# PCBv4.net
KiCad netlist of a schematic drawn in Altium Designer
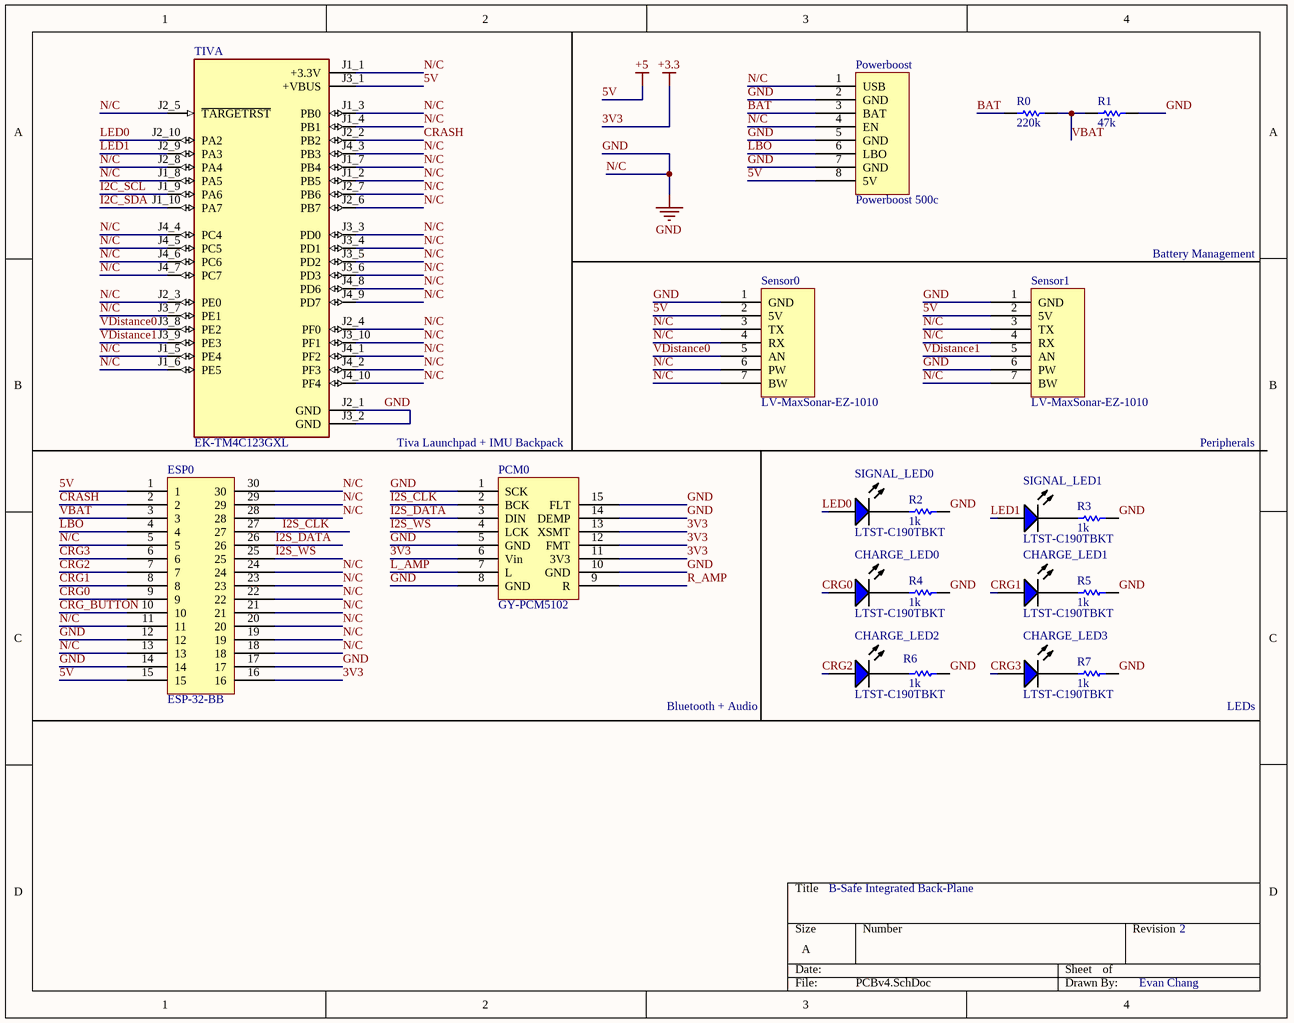
[diagram p0: PCBv4.SchDoc]

(export (version "E")
  (design (tool "Eeschema 10.0.6"))
  (components
    (comp (ref "CHARGE_LED0")
      (value "LTST-C190TBKT")
      (footprint "LTST-C190TBKT-2_V")
      (description "LED Uni-Color Blue, 76 mW, 20 mA, -20 to 80 degC, 2-Pin SMD, RoHS, Tape and Reel")
      (fields (field (name "MANUFACTURER") "Lite-On"))
      (libsource (lib "Evan Chang work on PCB") (part "LED-BLUE-AK-2"))
    )
    (comp (ref "CHARGE_LED1")
      (value "LTST-C190TBKT")
      (footprint "LTST-C190TBKT-2_V")
      (description "LED Uni-Color Blue, 76 mW, 20 mA, -20 to 80 degC, 2-Pin SMD, RoHS, Tape and Reel")
      (fields (field (name "MANUFACTURER") "Lite-On"))
      (libsource (lib "Evan Chang work on PCB") (part "LED-BLUE-AK-2"))
    )
    (comp (ref "CHARGE_LED2")
      (value "LTST-C190TBKT")
      (footprint "LTST-C190TBKT-2_V")
      (description "LED Uni-Color Blue, 76 mW, 20 mA, -20 to 80 degC, 2-Pin SMD, RoHS, Tape and Reel")
      (fields (field (name "MANUFACTURER") "Lite-On"))
      (libsource (lib "Evan Chang work on PCB") (part "LED-BLUE-AK-2"))
    )
    (comp (ref "CHARGE_LED3")
      (value "LTST-C190TBKT")
      (footprint "LTST-C190TBKT-2_V")
      (description "LED Uni-Color Blue, 76 mW, 20 mA, -20 to 80 degC, 2-Pin SMD, RoHS, Tape and Reel")
      (fields (field (name "MANUFACTURER") "Lite-On"))
      (libsource (lib "Evan Chang work on PCB") (part "LED-BLUE-AK-2"))
    )
    (comp (ref "ESP0")
      (value "ESP-32-BB")
      (footprint "ESP-32-BB-Footprint-1")
      (description "Breakoutboard for ESP-32-BB")
      (libsource (lib "Evan Chang work on PCB") (part "ESP-32-BB-Symbol-1"))
    )
    (comp (ref "PCM0")
      (value "GY-PCM5102")
      (footprint "GY-PCM5102-Footprint-1")
      (description "breakout board for pcm")
      (libsource (lib "Evan Chang work on PCB") (part "GY-PCM5102-Symbol-1"))
    )
    (comp (ref "Powerboost")
      (value "Powerboost 500c")
      (footprint "Powerboost 500c-Footprint-1")
      (description "Breakout board component for Adafruit Powerboost 500c")
      (libsource (lib "Evan Chang work on PCB") (part "Powerboost 500c-Symbol-1"))
    )
    (comp (ref "R0")
      (value "220k")
      (footprint "RESC1005X40X25ML05T10")
      (description "Chip Resistor, 51 KOhm, +/- 5%, 0.063 W, -55 to 155 degC, 0402 (1005 Metric)")
      (fields (field (name "POWER") "63mW") (field (name "TOLERANCE") "5%"))
      (libsource (lib "Evan Chang work on PCB") (part "RES-2"))
    )
    (comp (ref "R1")
      (value "47k")
      (footprint "RESC1005X40X25ML05T10")
      (description "Chip Resistor, 51 KOhm, +/- 5%, 0.063 W, -55 to 155 degC, 0402 (1005 Metric)")
      (fields (field (name "POWER") "63mW") (field (name "TOLERANCE") "5%"))
      (libsource (lib "Evan Chang work on PCB") (part "RES-2"))
    )
    (comp (ref "R2")
      (value "1k")
      (footprint "RESC3116X70X50ML13T20")
      (description "Chip Resistor, 1 KOhm, +/- 1%, 0.25 W, -55 to 155 degC, 1206 (3216 Metric)")
      (fields (field (name "TOLERANCE") "1%") (field (name "POWER") "250mW"))
      (libsource (lib "Evan Chang work on PCB") (part "RES-2"))
    )
    (comp (ref "R3")
      (value "1k")
      (footprint "RESC3116X70X50ML13T20")
      (description "Chip Resistor, 1 KOhm, +/- 1%, 0.25 W, -55 to 155 degC, 1206 (3216 Metric)")
      (fields (field (name "TOLERANCE") "1%") (field (name "POWER") "250mW"))
      (libsource (lib "Evan Chang work on PCB") (part "RES-2"))
    )
    (comp (ref "R4")
      (value "1k")
      (footprint "RESC3116X70X50ML13T20")
      (description "Chip Resistor, 1 KOhm, +/- 1%, 0.25 W, -55 to 155 degC, 1206 (3216 Metric)")
      (fields (field (name "TOLERANCE") "1%") (field (name "POWER") "250mW"))
      (libsource (lib "Evan Chang work on PCB") (part "RES-2"))
    )
    (comp (ref "R5")
      (value "1k")
      (footprint "RESC3116X70X50ML13T20")
      (description "Chip Resistor, 1 KOhm, +/- 1%, 0.25 W, -55 to 155 degC, 1206 (3216 Metric)")
      (fields (field (name "TOLERANCE") "1%") (field (name "POWER") "250mW"))
      (libsource (lib "Evan Chang work on PCB") (part "RES-2"))
    )
    (comp (ref "R6")
      (value "1k")
      (footprint "RESC3116X70X50ML13T20")
      (description "Chip Resistor, 1 KOhm, +/- 1%, 0.25 W, -55 to 155 degC, 1206 (3216 Metric)")
      (fields (field (name "TOLERANCE") "1%") (field (name "POWER") "250mW"))
      (libsource (lib "Evan Chang work on PCB") (part "RES-2"))
    )
    (comp (ref "R7")
      (value "1k")
      (footprint "RESC3116X70X50ML13T20")
      (description "Chip Resistor, 1 KOhm, +/- 1%, 0.25 W, -55 to 155 degC, 1206 (3216 Metric)")
      (fields (field (name "TOLERANCE") "1%") (field (name "POWER") "250mW"))
      (libsource (lib "Evan Chang work on PCB") (part "RES-2"))
    )
    (comp (ref "Sensor0")
      (value "LV-MaxSonar-EZ-1010")
      (footprint "LV-MaxSonar-EZ-1010-Footprint-1")
      (description "Ultrasonic sensor")
      (libsource (lib "Evan Chang work on PCB") (part "LV-Ma-Symbol-1"))
    )
    (comp (ref "Sensor1")
      (value "LV-MaxSonar-EZ-1010")
      (footprint "LV-MaxSonar-EZ-1010-Footprint-1")
      (description "Ultrasonic sensor")
      (libsource (lib "Evan Chang work on PCB") (part "LV-Ma-Symbol-1"))
    )
    (comp (ref "SIGNAL_LED0")
      (value "LTST-C190TBKT")
      (footprint "LTST-C190TBKT-2_V")
      (description "LED Uni-Color Blue, 76 mW, 20 mA, -20 to 80 degC, 2-Pin SMD, RoHS, Tape and Reel")
      (fields (field (name "MANUFACTURER") "Lite-On"))
      (libsource (lib "Evan Chang work on PCB") (part "LED-BLUE-AK-2"))
    )
    (comp (ref "SIGNAL_LED1")
      (value "LTST-C190TBKT")
      (footprint "LTST-C190TBKT-2_V")
      (description "LED Uni-Color Blue, 76 mW, 20 mA, -20 to 80 degC, 2-Pin SMD, RoHS, Tape and Reel")
      (fields (field (name "MANUFACTURER") "Lite-On"))
      (libsource (lib "Evan Chang work on PCB") (part "LED-BLUE-AK-2"))
    )
    (comp (ref "TIVA")
      (value "EK-TM4C123GXL")
      (footprint "MODULE_EK-TM4C123GXL")
      (description "ARMÂ® CortexÂ®-M4F Based MCU TM4C123G LaunchPadâ„¢ Evaluation Kit")
      (fields (field (name "MF") "Texas Instruments"))
      (libsource (lib "EK-TM4C123GXL") (part "EK-TM4C123GXL"))
    )
  )
  (nets
    (net (code "1") (name "+3.3") (class "Default")
      (node (ref "ESP0") (pin "16") (pinfunction "16_16") (pintype "passive"))
      (node (ref "PCM0") (pin "11") (pinfunction "3V3_11") (pintype "passive"))
      (node (ref "PCM0") (pin "12") (pinfunction "FMT_12") (pintype "passive"))
      (node (ref "PCM0") (pin "13") (pinfunction "XSMT_13") (pintype "passive"))
      (node (ref "PCM0") (pin "6") (pinfunction "Vin_6") (pintype "passive"))
    )
    (net (code "2") (name "+5") (class "Default")
      (node (ref "ESP0") (pin "1") (pinfunction "1_1") (pintype "passive"))
      (node (ref "ESP0") (pin "15") (pinfunction "15_15") (pintype "passive"))
      (node (ref "Powerboost") (pin "8") (pinfunction "5V_8") (pintype "passive"))
      (node (ref "Sensor0") (pin "2") (pinfunction "5V_2") (pintype "passive"))
      (node (ref "Sensor1") (pin "2") (pinfunction "5V_2") (pintype "passive"))
      (node (ref "TIVA") (pin "J3_1") (pinfunction "+VBUS_J3_1") (pintype "power_in"))
    )
    (net (code "3") (name "/BAT") (class "Default")
      (node (ref "Powerboost") (pin "3") (pinfunction "BAT_3") (pintype "passive"))
      (node (ref "R0") (pin "1") (pinfunction "1_1") (pintype "passive"))
    )
    (net (code "4") (name "/CRASH") (class "Default")
      (node (ref "ESP0") (pin "2") (pinfunction "2_2") (pintype "passive"))
      (node (ref "TIVA") (pin "J2_2") (pinfunction "PB2_J2_2") (pintype "bidirectional"))
    )
    (net (code "5") (name "/CRG0") (class "Default")
      (node (ref "CHARGE_LED0") (pin "1") (pinfunction "A_1") (pintype "passive"))
      (node (ref "ESP0") (pin "9") (pinfunction "9_9") (pintype "passive"))
    )
    (net (code "6") (name "/CRG1") (class "Default")
      (node (ref "CHARGE_LED1") (pin "1") (pinfunction "A_1") (pintype "passive"))
      (node (ref "ESP0") (pin "8") (pinfunction "8_8") (pintype "passive"))
    )
    (net (code "7") (name "/CRG2") (class "Default")
      (node (ref "CHARGE_LED2") (pin "1") (pinfunction "A_1") (pintype "passive"))
      (node (ref "ESP0") (pin "7") (pinfunction "7_7") (pintype "passive"))
    )
    (net (code "8") (name "/CRG3") (class "Default")
      (node (ref "CHARGE_LED3") (pin "1") (pinfunction "A_1") (pintype "passive"))
      (node (ref "ESP0") (pin "6") (pinfunction "6_6") (pintype "passive"))
    )
    (net (code "9") (name "/CRG_BUTTON") (class "Default")
      (node (ref "ESP0") (pin "10") (pinfunction "10_10") (pintype "passive"))
    )
    (net (code "10") (name "/I2C_SCL") (class "Default")
      (node (ref "TIVA") (pin "J1_9") (pinfunction "PA6_J1_9") (pintype "bidirectional"))
    )
    (net (code "11") (name "/I2C_SDA") (class "Default")
      (node (ref "TIVA") (pin "J1_10") (pinfunction "PA7_J1_10") (pintype "bidirectional"))
    )
    (net (code "12") (name "/I2S_CLK") (class "Default")
      (node (ref "ESP0") (pin "27") (pinfunction "27_27") (pintype "passive"))
      (node (ref "PCM0") (pin "2") (pinfunction "BCK_2") (pintype "passive"))
    )
    (net (code "13") (name "/I2S_DATA") (class "Default")
      (node (ref "ESP0") (pin "26") (pinfunction "26_26") (pintype "passive"))
      (node (ref "PCM0") (pin "3") (pinfunction "DIN_3") (pintype "passive"))
    )
    (net (code "14") (name "/I2S_WS") (class "Default")
      (node (ref "ESP0") (pin "25") (pinfunction "25_25") (pintype "passive"))
      (node (ref "PCM0") (pin "4") (pinfunction "LCK_4") (pintype "passive"))
    )
    (net (code "15") (name "/LBO") (class "Default")
      (node (ref "ESP0") (pin "4") (pinfunction "4_4") (pintype "passive"))
      (node (ref "Powerboost") (pin "6") (pinfunction "LBO_6") (pintype "passive"))
    )
    (net (code "16") (name "/LED0") (class "Default")
      (node (ref "SIGNAL_LED0") (pin "1") (pinfunction "A_1") (pintype "passive"))
      (node (ref "TIVA") (pin "J2_10") (pinfunction "PA2_J2_10") (pintype "bidirectional"))
    )
    (net (code "17") (name "/LED1") (class "Default")
      (node (ref "SIGNAL_LED1") (pin "1") (pinfunction "A_1") (pintype "passive"))
      (node (ref "TIVA") (pin "J2_9") (pinfunction "PA3_J2_9") (pintype "bidirectional"))
    )
    (net (code "18") (name "/L_AMP") (class "Default")
      (node (ref "PCM0") (pin "7") (pinfunction "L_7") (pintype "passive"))
    )
    (net (code "19") (name "/R_AMP") (class "Default")
      (node (ref "PCM0") (pin "9") (pinfunction "R_9") (pintype "passive"))
    )
    (net (code "20") (name "/VBAT") (class "Default")
      (node (ref "ESP0") (pin "3") (pinfunction "3_3") (pintype "passive"))
      (node (ref "R0") (pin "2") (pinfunction "2_2") (pintype "passive"))
      (node (ref "R1") (pin "1") (pinfunction "1_1") (pintype "passive"))
    )
    (net (code "21") (name "/VDistance0") (class "Default")
      (node (ref "Sensor0") (pin "5") (pinfunction "AN_5") (pintype "passive"))
      (node (ref "TIVA") (pin "J3_8") (pinfunction "PE2_J3_8") (pintype "bidirectional"))
    )
    (net (code "22") (name "/VDistance1") (class "Default")
      (node (ref "Sensor1") (pin "5") (pinfunction "AN_5") (pintype "passive"))
      (node (ref "TIVA") (pin "J3_9") (pinfunction "PE3_J3_9") (pintype "bidirectional"))
    )
    (net (code "23") (name "GND") (class "Default")
      (node (ref "ESP0") (pin "11") (pinfunction "11_11") (pintype "passive"))
      (node (ref "ESP0") (pin "12") (pinfunction "12_12") (pintype "passive"))
      (node (ref "ESP0") (pin "13") (pinfunction "13_13") (pintype "passive"))
      (node (ref "ESP0") (pin "14") (pinfunction "14_14") (pintype "passive"))
      (node (ref "ESP0") (pin "17") (pinfunction "17_17") (pintype "passive"))
      (node (ref "ESP0") (pin "18") (pinfunction "18_18") (pintype "passive"))
      (node (ref "ESP0") (pin "19") (pinfunction "19_19") (pintype "passive"))
      (node (ref "ESP0") (pin "20") (pinfunction "20_20") (pintype "passive"))
      (node (ref "ESP0") (pin "21") (pinfunction "21_21") (pintype "passive"))
      (node (ref "ESP0") (pin "22") (pinfunction "22_22") (pintype "passive"))
      (node (ref "ESP0") (pin "23") (pinfunction "23_23") (pintype "passive"))
      (node (ref "ESP0") (pin "24") (pinfunction "24_24") (pintype "passive"))
      (node (ref "ESP0") (pin "28") (pinfunction "28_28") (pintype "passive"))
      (node (ref "ESP0") (pin "29") (pinfunction "29_29") (pintype "passive"))
      (node (ref "ESP0") (pin "30") (pinfunction "30_30") (pintype "passive"))
      (node (ref "ESP0") (pin "5") (pinfunction "5_5") (pintype "passive"))
      (node (ref "PCM0") (pin "1") (pinfunction "SCK_1") (pintype "passive"))
      (node (ref "PCM0") (pin "10") (pinfunction "GND_10") (pintype "passive"))
      (node (ref "PCM0") (pin "14") (pinfunction "DEMP_14") (pintype "passive"))
      (node (ref "PCM0") (pin "15") (pinfunction "FLT_15") (pintype "passive"))
      (node (ref "PCM0") (pin "5") (pinfunction "GND_5") (pintype "passive"))
      (node (ref "PCM0") (pin "8") (pinfunction "GND_8") (pintype "passive"))
      (node (ref "Powerboost") (pin "1") (pinfunction "USB_1") (pintype "passive"))
      (node (ref "Powerboost") (pin "2") (pinfunction "GND_2") (pintype "passive"))
      (node (ref "Powerboost") (pin "4") (pinfunction "EN_4") (pintype "passive"))
      (node (ref "Powerboost") (pin "5") (pinfunction "GND_5") (pintype "passive"))
      (node (ref "Powerboost") (pin "7") (pinfunction "GND_7") (pintype "passive"))
      (node (ref "R1") (pin "2") (pinfunction "2_2") (pintype "passive"))
      (node (ref "R2") (pin "2") (pinfunction "2_2") (pintype "passive"))
      (node (ref "R3") (pin "2") (pinfunction "2_2") (pintype "passive"))
      (node (ref "R4") (pin "2") (pinfunction "2_2") (pintype "passive"))
      (node (ref "R5") (pin "2") (pinfunction "2_2") (pintype "passive"))
      (node (ref "R6") (pin "2") (pinfunction "2_2") (pintype "passive"))
      (node (ref "R7") (pin "2") (pinfunction "2_2") (pintype "passive"))
      (node (ref "Sensor0") (pin "1") (pinfunction "GND_1") (pintype "passive"))
      (node (ref "Sensor0") (pin "3") (pinfunction "TX_3") (pintype "passive"))
      (node (ref "Sensor0") (pin "4") (pinfunction "RX_4") (pintype "passive"))
      (node (ref "Sensor0") (pin "6") (pinfunction "PW_6") (pintype "passive"))
      (node (ref "Sensor0") (pin "7") (pinfunction "BW_7") (pintype "passive"))
      (node (ref "Sensor1") (pin "1") (pinfunction "GND_1") (pintype "passive"))
      (node (ref "Sensor1") (pin "3") (pinfunction "TX_3") (pintype "passive"))
      (node (ref "Sensor1") (pin "4") (pinfunction "RX_4") (pintype "passive"))
      (node (ref "Sensor1") (pin "6") (pinfunction "PW_6") (pintype "passive"))
      (node (ref "Sensor1") (pin "7") (pinfunction "BW_7") (pintype "passive"))
      (node (ref "TIVA") (pin "J1_1") (pinfunction "+3.3V_J1_1") (pintype "power_in"))
      (node (ref "TIVA") (pin "J1_2") (pinfunction "PB5_J1_2") (pintype "bidirectional"))
      (node (ref "TIVA") (pin "J1_3") (pinfunction "PB0_J1_3") (pintype "bidirectional"))
      (node (ref "TIVA") (pin "J1_4") (pinfunction "PB1_J1_4") (pintype "bidirectional"))
      (node (ref "TIVA") (pin "J1_5") (pinfunction "PE4_J1_5") (pintype "bidirectional"))
      (node (ref "TIVA") (pin "J1_6") (pinfunction "PE5_J1_6") (pintype "bidirectional"))
      (node (ref "TIVA") (pin "J1_7") (pinfunction "PB4_J1_7") (pintype "bidirectional"))
      (node (ref "TIVA") (pin "J1_8") (pinfunction "PA5_J1_8") (pintype "bidirectional"))
      (node (ref "TIVA") (pin "J2_1") (pinfunction "GND_J2_1") (pintype "power_in"))
      (node (ref "TIVA") (pin "J2_3") (pinfunction "PE0_J2_3") (pintype "bidirectional"))
      (node (ref "TIVA") (pin "J2_4") (pinfunction "PF0_J2_4") (pintype "bidirectional"))
      (node (ref "TIVA") (pin "J2_5") (pinfunction "~{TARGETRST}_J2_5") (pintype "input"))
      (node (ref "TIVA") (pin "J2_6") (pinfunction "PB7_J2_6") (pintype "bidirectional"))
      (node (ref "TIVA") (pin "J2_7") (pinfunction "PB6_J2_7") (pintype "bidirectional"))
      (node (ref "TIVA") (pin "J2_8") (pinfunction "PA4_J2_8") (pintype "bidirectional"))
      (node (ref "TIVA") (pin "J3_10") (pinfunction "PF1_J3_10") (pintype "bidirectional"))
      (node (ref "TIVA") (pin "J3_2") (pinfunction "GND_J3_2") (pintype "power_in"))
      (node (ref "TIVA") (pin "J3_3") (pinfunction "PD0_J3_3") (pintype "bidirectional"))
      (node (ref "TIVA") (pin "J3_4") (pinfunction "PD1_J3_4") (pintype "bidirectional"))
      (node (ref "TIVA") (pin "J3_5") (pinfunction "PD2_J3_5") (pintype "bidirectional"))
      (node (ref "TIVA") (pin "J3_6") (pinfunction "PD3_J3_6") (pintype "bidirectional"))
      (node (ref "TIVA") (pin "J3_7") (pinfunction "PE1_J3_7") (pintype "bidirectional"))
      (node (ref "TIVA") (pin "J4_1") (pinfunction "PF2_J4_1") (pintype "bidirectional"))
      (node (ref "TIVA") (pin "J4_10") (pinfunction "PF4_J4_10") (pintype "bidirectional"))
      (node (ref "TIVA") (pin "J4_2") (pinfunction "PF3_J4_2") (pintype "bidirectional"))
      (node (ref "TIVA") (pin "J4_3") (pinfunction "PB3_J4_3") (pintype "bidirectional"))
      (node (ref "TIVA") (pin "J4_4") (pinfunction "PC4_J4_4") (pintype "bidirectional"))
      (node (ref "TIVA") (pin "J4_5") (pinfunction "PC5_J4_5") (pintype "bidirectional"))
      (node (ref "TIVA") (pin "J4_6") (pinfunction "PC6_J4_6") (pintype "bidirectional"))
      (node (ref "TIVA") (pin "J4_7") (pinfunction "PC7_J4_7") (pintype "bidirectional"))
      (node (ref "TIVA") (pin "J4_8") (pinfunction "PD6_J4_8") (pintype "bidirectional"))
      (node (ref "TIVA") (pin "J4_9") (pinfunction "PD7_J4_9") (pintype "bidirectional"))
    )
    (net (code "24") (name "Net-(CHARGE_LED0-K)") (class "Default")
      (node (ref "CHARGE_LED0") (pin "2") (pinfunction "K_2") (pintype "passive"))
      (node (ref "R4") (pin "1") (pinfunction "1_1") (pintype "passive"))
    )
    (net (code "25") (name "Net-(CHARGE_LED1-K)") (class "Default")
      (node (ref "CHARGE_LED1") (pin "2") (pinfunction "K_2") (pintype "passive"))
      (node (ref "R5") (pin "1") (pinfunction "1_1") (pintype "passive"))
    )
    (net (code "26") (name "Net-(CHARGE_LED2-K)") (class "Default")
      (node (ref "CHARGE_LED2") (pin "2") (pinfunction "K_2") (pintype "passive"))
      (node (ref "R6") (pin "1") (pinfunction "1_1") (pintype "passive"))
    )
    (net (code "27") (name "Net-(CHARGE_LED3-K)") (class "Default")
      (node (ref "CHARGE_LED3") (pin "2") (pinfunction "K_2") (pintype "passive"))
      (node (ref "R7") (pin "1") (pinfunction "1_1") (pintype "passive"))
    )
    (net (code "28") (name "Net-(SIGNAL_LED0-K)") (class "Default")
      (node (ref "R2") (pin "1") (pinfunction "1_1") (pintype "passive"))
      (node (ref "SIGNAL_LED0") (pin "2") (pinfunction "K_2") (pintype "passive"))
    )
    (net (code "29") (name "Net-(SIGNAL_LED1-K)") (class "Default")
      (node (ref "R3") (pin "1") (pinfunction "1_1") (pintype "passive"))
      (node (ref "SIGNAL_LED1") (pin "2") (pinfunction "K_2") (pintype "passive"))
    )
  )
)
